# Peripherals.net
KiCad netlist of a schematic drawn in Altium Designer
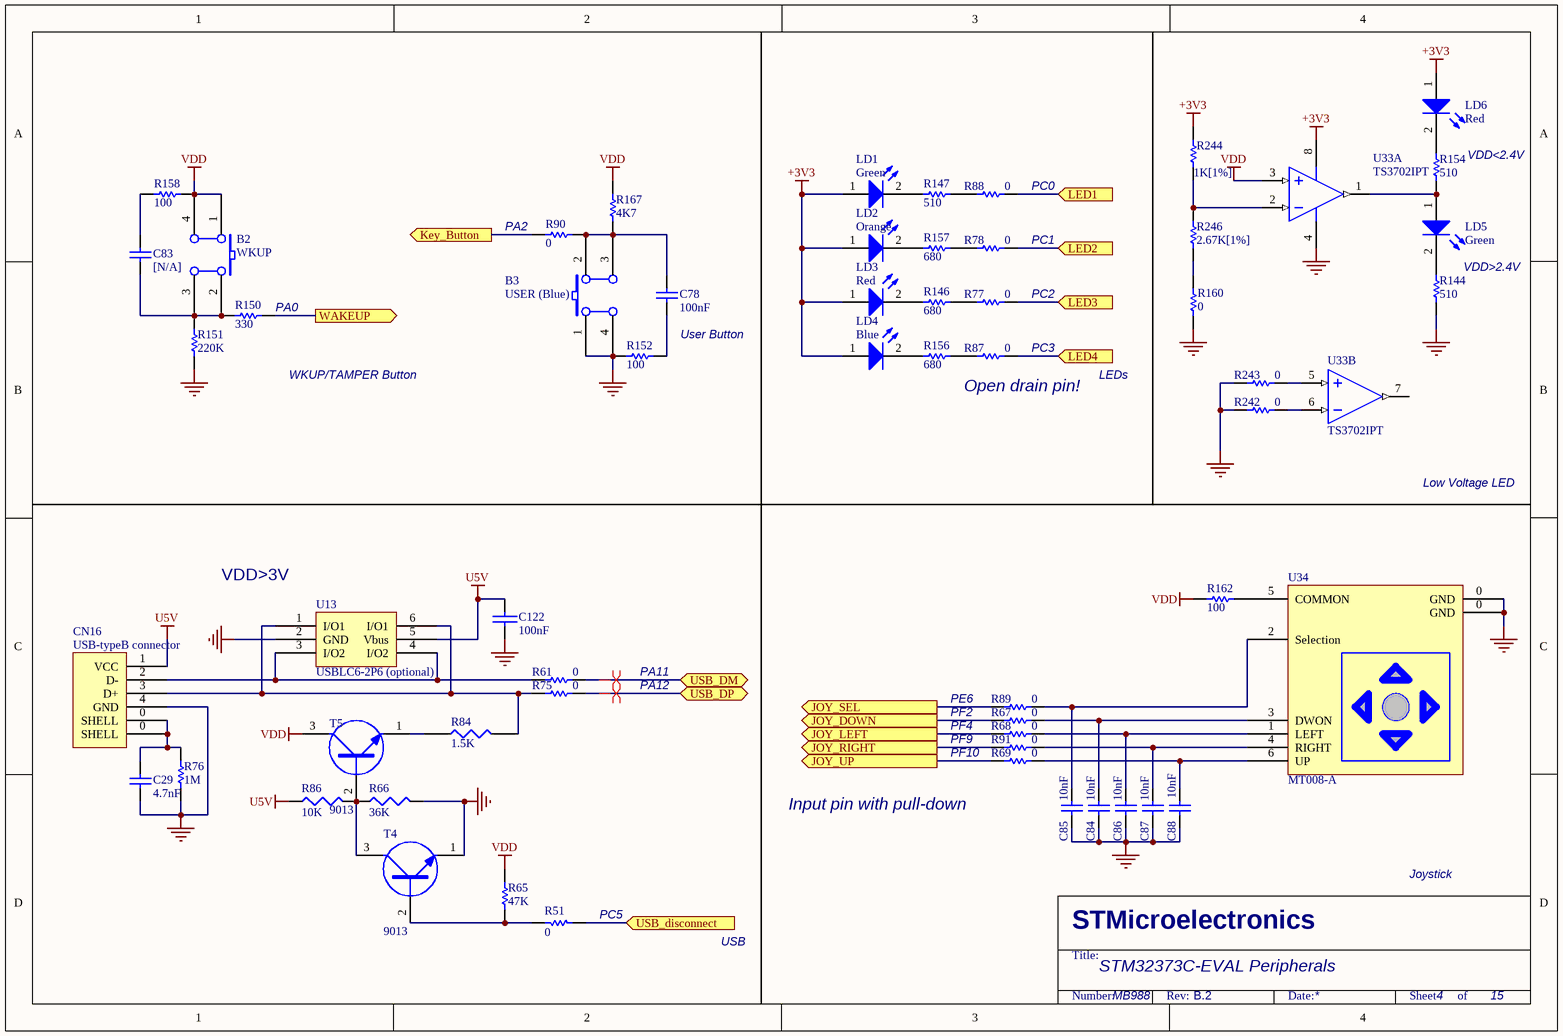
[diagram p0: Peripherals.SchDoc]

(export (version "E")
  (design (tool "Eeschema 10.0.6"))
  (components
    (comp (ref "B2")
      (value "WKUP")
      (footprint "PB10")
      (description "SE PUSHBUTTON")
      (libsource (lib "Documents") (part "SW PUSHBUTTON"))
    )
    (comp (ref "B3")
      (value "USER (Blue)")
      (footprint "PB10")
      (description "SE PUSHBUTTON")
      (libsource (lib "Documents") (part "SW PUSHBUTTON"))
    )
    (comp (ref "C29")
      (value "4.7nF")
      (footprint "0603C")
      (description "Capacitor")
      (fields (field (name "PUBLISHER") "Altium Limited"))
      (libsource (lib "Miscellaneous Devices") (part "CAP"))
    )
    (comp (ref "C78")
      (value "100nF")
      (footprint "0603C")
      (description "Capacitor")
      (fields (field (name "PUBLISHER") "Altium Limited"))
      (libsource (lib "Miscellaneous Devices") (part "CAP"))
    )
    (comp (ref "C83")
      (value "[N/A]")
      (footprint "0603C")
      (description "Capacitor")
      (fields (field (name "PUBLISHER") "Altium Limited"))
      (libsource (lib "Miscellaneous Devices") (part "CAP"))
    )
    (comp (ref "C84")
      (value "10nF")
      (footprint "0603C")
      (description "Capacitor")
      (fields (field (name "PUBLISHER") "Altium Limited"))
      (libsource (lib "Miscellaneous Devices") (part "CAP"))
    )
    (comp (ref "C85")
      (value "10nF")
      (footprint "0603C")
      (description "Capacitor")
      (fields (field (name "PUBLISHER") "Altium Limited"))
      (libsource (lib "Miscellaneous Devices") (part "CAP"))
    )
    (comp (ref "C86")
      (value "10nF")
      (footprint "0603C")
      (description "Capacitor")
      (fields (field (name "PUBLISHER") "Altium Limited"))
      (libsource (lib "Miscellaneous Devices") (part "CAP"))
    )
    (comp (ref "C87")
      (value "10nF")
      (footprint "0603C")
      (description "Capacitor")
      (fields (field (name "PUBLISHER") "Altium Limited"))
      (libsource (lib "Miscellaneous Devices") (part "CAP"))
    )
    (comp (ref "C88")
      (value "10nF")
      (footprint "0603C")
      (description "Capacitor")
      (fields (field (name "PUBLISHER") "Altium Limited"))
      (libsource (lib "Miscellaneous Devices") (part "CAP"))
    )
    (comp (ref "C122")
      (value "100nF")
      (footprint "0603C")
      (description "Capacitor")
      (libsource (lib "*") (part "CAP"))
    )
    (comp (ref "CN16")
      (value "USB-typeB connector")
      (footprint "USB-B")
      (description "USB-B")
      (libsource (lib "Documents") (part "USB-B"))
    )
    (comp (ref "LD1")
      (value "Green")
      (footprint "0603D")
      (description "Typical RED, GREEN, YELLOW, AMBER GaAs LED")
      (fields (field (name "PUBLISHER") "Altium Limited"))
      (libsource (lib "Miscellaneous Devices") (part "LED2"))
    )
    (comp (ref "LD2")
      (value "Orange")
      (footprint "0603D")
      (description "Typical RED, GREEN, YELLOW, AMBER GaAs LED")
      (fields (field (name "PUBLISHER") "Altium Limited"))
      (libsource (lib "Miscellaneous Devices") (part "LED2"))
    )
    (comp (ref "LD3")
      (value "Red")
      (footprint "0603D")
      (description "Typical RED, GREEN, YELLOW, AMBER GaAs LED")
      (fields (field (name "PUBLISHER") "Altium Limited"))
      (libsource (lib "Miscellaneous Devices") (part "LED2"))
    )
    (comp (ref "LD4")
      (value "Blue")
      (footprint "0603D")
      (description "Typical RED, GREEN, YELLOW, AMBER GaAs LED")
      (fields (field (name "PUBLISHER") "Altium Limited"))
      (libsource (lib "Miscellaneous Devices") (part "LED2"))
    )
    (comp (ref "LD5")
      (value "Green")
      (footprint "0603D")
      (description "Typical RED, GREEN, YELLOW, AMBER GaAs LED")
      (fields (field (name "PUBLISHER") "Altium Limited"))
      (libsource (lib "Miscellaneous Devices") (part "LED2"))
    )
    (comp (ref "LD6")
      (value "Red")
      (footprint "0603D")
      (description "Typical RED, GREEN, YELLOW, AMBER GaAs LED")
      (fields (field (name "PUBLISHER") "Altium Limited"))
      (libsource (lib "Miscellaneous Devices") (part "LED2"))
    )
    (comp (ref "R51")
      (value "0")
      (footprint "0603R")
      (description "Resistor")
      (fields (field (name "PUBLISHER") "Altium Limited"))
      (libsource (lib "Miscellaneous Devices") (part "Res1"))
    )
    (comp (ref "R61")
      (value "0")
      (footprint "0603R")
      (description "Resistor")
      (fields (field (name "PUBLISHER") "Altium Limited"))
      (libsource (lib "Miscellaneous Devices") (part "Res1"))
    )
    (comp (ref "R65")
      (value "47K")
      (footprint "0603R")
      (description "Resistor")
      (fields (field (name "PUBLISHER") "Altium Limited"))
      (libsource (lib "Miscellaneous Devices") (part "Res1"))
    )
    (comp (ref "R66") (value "36K") (footprint "0603R") (libsource (lib "*") (part "R")))
    (comp (ref "R67")
      (value "0")
      (footprint "0603R")
      (description "Resistor")
      (fields (field (name "PUBLISHER") "Altium Limited"))
      (libsource (lib "Miscellaneous Devices") (part "Res1"))
    )
    (comp (ref "R68")
      (value "0")
      (footprint "0603R")
      (description "Resistor")
      (fields (field (name "PUBLISHER") "Altium Limited"))
      (libsource (lib "Miscellaneous Devices") (part "Res1"))
    )
    (comp (ref "R69")
      (value "0")
      (footprint "0603R")
      (description "Resistor")
      (fields (field (name "PUBLISHER") "Altium Limited"))
      (libsource (lib "Miscellaneous Devices") (part "Res1"))
    )
    (comp (ref "R75")
      (value "0")
      (footprint "0603R")
      (description "Resistor")
      (fields (field (name "PUBLISHER") "Altium Limited"))
      (libsource (lib "Miscellaneous Devices") (part "Res1"))
    )
    (comp (ref "R76")
      (value "1M")
      (footprint "0603R")
      (description "Resistor")
      (fields (field (name "PUBLISHER") "Altium Limited"))
      (libsource (lib "Miscellaneous Devices") (part "Res1"))
    )
    (comp (ref "R77")
      (value "0")
      (footprint "0603R")
      (description "Resistor")
      (fields (field (name "PUBLISHER") "Altium Limited"))
      (libsource (lib "Miscellaneous Devices") (part "Res1"))
    )
    (comp (ref "R78")
      (value "0")
      (footprint "0603R")
      (description "Resistor")
      (fields (field (name "PUBLISHER") "Altium Limited"))
      (libsource (lib "Miscellaneous Devices") (part "Res1"))
    )
    (comp (ref "R84") (value "1.5K") (footprint "0603R") (libsource (lib "*") (part "RES1")))
    (comp (ref "R86") (value "10K") (footprint "0603R") (libsource (lib "*") (part "R")))
    (comp (ref "R87")
      (value "0")
      (footprint "0603R")
      (description "Resistor")
      (fields (field (name "PUBLISHER") "Altium Limited"))
      (libsource (lib "Miscellaneous Devices") (part "Res1"))
    )
    (comp (ref "R88")
      (value "0")
      (footprint "0603R")
      (description "Resistor")
      (fields (field (name "PUBLISHER") "Altium Limited"))
      (libsource (lib "Miscellaneous Devices") (part "Res1"))
    )
    (comp (ref "R89")
      (value "0")
      (footprint "0603R")
      (description "Resistor")
      (fields (field (name "PUBLISHER") "Altium Limited"))
      (libsource (lib "Miscellaneous Devices") (part "Res1"))
    )
    (comp (ref "R90")
      (value "0")
      (footprint "0603R")
      (description "Resistor")
      (fields (field (name "PUBLISHER") "Altium Limited"))
      (libsource (lib "Miscellaneous Devices") (part "Res1"))
    )
    (comp (ref "R91")
      (value "0")
      (footprint "0603R")
      (description "Resistor")
      (fields (field (name "PUBLISHER") "Altium Limited"))
      (libsource (lib "Miscellaneous Devices") (part "Res1"))
    )
    (comp (ref "R144")
      (value "510")
      (footprint "0603R")
      (description "Resistor")
      (fields (field (name "PUBLISHER") "Altium Limited"))
      (libsource (lib "Miscellaneous Devices") (part "Res1"))
    )
    (comp (ref "R146")
      (value "680")
      (footprint "0603R")
      (description "Resistor")
      (fields (field (name "PUBLISHER") "Altium Limited"))
      (libsource (lib "Miscellaneous Devices") (part "Res1"))
    )
    (comp (ref "R147")
      (value "510")
      (footprint "0603R")
      (description "Resistor")
      (fields (field (name "PUBLISHER") "Altium Limited"))
      (libsource (lib "Miscellaneous Devices") (part "Res1"))
    )
    (comp (ref "R150")
      (value "330")
      (footprint "0603R")
      (description "Resistor")
      (fields (field (name "PUBLISHER") "Altium Limited"))
      (libsource (lib "Miscellaneous Devices") (part "Res1"))
    )
    (comp (ref "R151")
      (value "220K")
      (footprint "0603R")
      (description "Resistor")
      (fields (field (name "PUBLISHER") "Altium Limited"))
      (libsource (lib "Miscellaneous Devices") (part "res1"))
    )
    (comp (ref "R152")
      (value "100")
      (footprint "0603R")
      (description "Resistor")
      (fields (field (name "PUBLISHER") "Altium Limited"))
      (libsource (lib "Miscellaneous Devices") (part "Res1"))
    )
    (comp (ref "R154")
      (value "510")
      (footprint "0603R")
      (description "Resistor")
      (fields (field (name "PUBLISHER") "Altium Limited"))
      (libsource (lib "Miscellaneous Devices") (part "Res1"))
    )
    (comp (ref "R156")
      (value "680")
      (footprint "0603R")
      (description "Resistor")
      (fields (field (name "PUBLISHER") "Altium Limited"))
      (libsource (lib "Miscellaneous Devices") (part "Res1"))
    )
    (comp (ref "R157")
      (value "680")
      (footprint "0603R")
      (description "Resistor")
      (fields (field (name "PUBLISHER") "Altium Limited"))
      (libsource (lib "Miscellaneous Devices") (part "Res1"))
    )
    (comp (ref "R158")
      (value "100")
      (footprint "0603R")
      (description "Resistor")
      (fields (field (name "PUBLISHER") "Altium Limited"))
      (libsource (lib "Miscellaneous Devices") (part "Res1"))
    )
    (comp (ref "R160")
      (value "0")
      (footprint "0603R")
      (description "Resistor")
      (fields (field (name "PUBLISHER") "Altium Limited"))
      (libsource (lib "Miscellaneous Devices") (part "Res1"))
    )
    (comp (ref "R162")
      (value "100")
      (footprint "0603R")
      (description "Resistor")
      (fields (field (name "PUBLISHER") "Altium Limited"))
      (libsource (lib "Miscellaneous Devices") (part "Res1"))
    )
    (comp (ref "R167")
      (value "4K7")
      (footprint "0603R")
      (description "Resistor")
      (fields (field (name "PUBLISHER") "Altium Limited"))
      (libsource (lib "Miscellaneous Devices") (part "res1"))
    )
    (comp (ref "R242")
      (value "0")
      (footprint "0603R")
      (description "Resistor")
      (fields (field (name "PUBLISHER") "Altium Limited"))
      (libsource (lib "Miscellaneous Devices") (part "Res1"))
    )
    (comp (ref "R243")
      (value "0")
      (footprint "0603R")
      (description "Resistor")
      (fields (field (name "PUBLISHER") "Altium Limited"))
      (libsource (lib "Miscellaneous Devices") (part "Res1"))
    )
    (comp (ref "R244")
      (value "1K[1%]")
      (footprint "0603R")
      (description "Resistor")
      (fields (field (name "PUBLISHER") "Altium Limited"))
      (libsource (lib "Miscellaneous Devices") (part "Res1"))
    )
    (comp (ref "R246")
      (value "2.67K[1%]")
      (footprint "0603R")
      (description "Resistor")
      (fields (field (name "PUBLISHER") "Altium Limited"))
      (libsource (lib "Miscellaneous Devices") (part "Res1"))
    )
    (comp (ref "T4") (value "9013") (footprint "SOT-23") (libsource (lib "*") (part "NPN")))
    (comp (ref "T5") (value "9013") (footprint "SOT-23") (libsource (lib "*") (part "NPN")))
    (comp (ref "U13")
      (value "USBLC6-2P6 (optional)")
      (footprint "SOT-666")
      (libsource (lib "STR910_SCHLIB") (part "USBLC6-2"))
    )
    (comp (ref "U33")
      (value "TS3702IPT")
      (footprint "TSSOP8(6.4)")
      (libsource (lib "MB819") (part "LM393PT"))
    )
    (comp (ref "U34") (value "MT008-A") (footprint "JOY") (libsource (lib "MB988") (part "MT-008A")))
  )
  (nets
    (net (code "1") (name "+3V3") (class "Default")
      (node (ref "LD1") (pin "1") (pinfunction "A_1") (pintype "passive"))
      (node (ref "LD2") (pin "1") (pinfunction "A_1") (pintype "passive"))
      (node (ref "LD3") (pin "1") (pinfunction "A_1") (pintype "passive"))
      (node (ref "LD4") (pin "1") (pinfunction "A_1") (pintype "passive"))
      (node (ref "LD6") (pin "1") (pinfunction "A_1") (pintype "passive"))
      (node (ref "R244") (pin "2") (pinfunction "2_2") (pintype "passive"))
      (node (ref "U33") (pin "8") (pinfunction "V+_8") (pintype "power_in"))
    )
    (net (code "2") (name "/JOY_DOWN") (class "Default")
      (node (ref "R67") (pin "2") (pinfunction "2_2") (pintype "passive"))
    )
    (net (code "3") (name "/JOY_LEFT") (class "Default")
      (node (ref "R68") (pin "2") (pinfunction "2_2") (pintype "passive"))
    )
    (net (code "4") (name "/JOY_RIGHT") (class "Default")
      (node (ref "R91") (pin "2") (pinfunction "2_2") (pintype "passive"))
    )
    (net (code "5") (name "/JOY_SEL") (class "Default")
      (node (ref "R89") (pin "2") (pinfunction "2_2") (pintype "passive"))
    )
    (net (code "6") (name "/JOY_UP") (class "Default")
      (node (ref "R69") (pin "2") (pinfunction "2_2") (pintype "passive"))
    )
    (net (code "7") (name "/Key_Button") (class "Default")
      (node (ref "R90") (pin "2") (pinfunction "2_2") (pintype "passive"))
    )
    (net (code "8") (name "/LED1") (class "Default")
      (node (ref "R88") (pin "1") (pinfunction "1_1") (pintype "passive"))
    )
    (net (code "9") (name "/LED2") (class "Default")
      (node (ref "R78") (pin "1") (pinfunction "1_1") (pintype "passive"))
    )
    (net (code "10") (name "/LED3") (class "Default")
      (node (ref "R77") (pin "1") (pinfunction "1_1") (pintype "passive"))
    )
    (net (code "11") (name "/LED4") (class "Default")
      (node (ref "R87") (pin "1") (pinfunction "1_1") (pintype "passive"))
    )
    (net (code "12") (name "/USB_DM") (class "Default")
      (node (ref "R61") (pin "1") (pinfunction "1_1") (pintype "passive"))
    )
    (net (code "13") (name "/USB_DP") (class "Default")
      (node (ref "R75") (pin "1") (pinfunction "1_1") (pintype "passive"))
    )
    (net (code "14") (name "/USB_disconnect") (class "Default")
      (node (ref "R51") (pin "2") (pinfunction "2_2") (pintype "passive"))
    )
    (net (code "15") (name "/WAKEUP") (class "Default")
      (node (ref "R150") (pin "2") (pinfunction "2_2") (pintype "passive"))
    )
    (net (code "16") (name "GND") (class "Default")
      (node (ref "B3") (pin "1") (pinfunction "A0_1") (pintype "passive"))
      (node (ref "B3") (pin "4") (pinfunction "A1_4") (pintype "passive"))
      (node (ref "C122") (pin "2") (pinfunction "2_2") (pintype "passive"))
      (node (ref "C29") (pin "1") (pinfunction "1_1") (pintype "passive"))
      (node (ref "C84") (pin "1") (pinfunction "1_1") (pintype "passive"))
      (node (ref "C85") (pin "1") (pinfunction "1_1") (pintype "passive"))
      (node (ref "C86") (pin "1") (pinfunction "1_1") (pintype "passive"))
      (node (ref "C87") (pin "1") (pinfunction "1_1") (pintype "passive"))
      (node (ref "C88") (pin "1") (pinfunction "1_1") (pintype "passive"))
      (node (ref "CN16") (pin "4") (pinfunction "GND_4") (pintype "passive"))
      (node (ref "R144") (pin "2") (pinfunction "2_2") (pintype "passive"))
      (node (ref "R151") (pin "2") (pinfunction "2_2") (pintype "passive"))
      (node (ref "R152") (pin "1") (pinfunction "1_1") (pintype "passive"))
      (node (ref "R160") (pin "2") (pinfunction "2_2") (pintype "passive"))
      (node (ref "R242") (pin "2") (pinfunction "2_2") (pintype "passive"))
      (node (ref "R243") (pin "2") (pinfunction "2_2") (pintype "passive"))
      (node (ref "R66") (pin "2") (pinfunction "2_2") (pintype "passive"))
      (node (ref "R76") (pin "1") (pinfunction "1_1") (pintype "passive"))
      (node (ref "T4") (pin "1") (pinfunction "E_1") (pintype "passive"))
      (node (ref "U13") (pin "2") (pinfunction "GND_2") (pintype "passive"))
      (node (ref "U33") (pin "4") (pinfunction "V-_4") (pintype "power_in"))
      (node (ref "U34") (pin "0") (pinfunction "GND_0") (pintype "passive"))
    )
    (net (code "17") (name "Net-(B2-B0)") (class "Default")
      (node (ref "B2") (pin "2") (pinfunction "B0_2") (pintype "passive"))
      (node (ref "B2") (pin "3") (pinfunction "B1_3") (pintype "passive"))
      (node (ref "C83") (pin "2") (pinfunction "2_2") (pintype "passive"))
      (node (ref "R150") (pin "1") (pinfunction "1_1") (pintype "passive"))
      (node (ref "R151") (pin "1") (pinfunction "1_1") (pintype "passive"))
    )
    (net (code "18") (name "Net-(B3-B0)") (class "Default")
      (node (ref "B3") (pin "2") (pinfunction "B0_2") (pintype "passive"))
      (node (ref "B3") (pin "3") (pinfunction "B1_3") (pintype "passive"))
      (node (ref "C78") (pin "2") (pinfunction "2_2") (pintype "passive"))
      (node (ref "R167") (pin "1") (pinfunction "1_1") (pintype "passive"))
      (node (ref "R90") (pin "1") (pinfunction "1_1") (pintype "passive"))
    )
    (net (code "19") (name "Net-(C78-Pad1)") (class "Default")
      (node (ref "C78") (pin "1") (pinfunction "1_1") (pintype "passive"))
      (node (ref "R152") (pin "2") (pinfunction "2_2") (pintype "passive"))
    )
    (net (code "20") (name "Net-(C83-Pad1)") (class "Default")
      (node (ref "C83") (pin "1") (pinfunction "1_1") (pintype "passive"))
      (node (ref "R158") (pin "2") (pinfunction "2_2") (pintype "passive"))
    )
    (net (code "21") (name "Net-(CN16-D+)") (class "Default")
      (node (ref "CN16") (pin "3") (pinfunction "D+_3") (pintype "passive"))
      (node (ref "R75") (pin "2") (pinfunction "2_2") (pintype "passive"))
      (node (ref "R84") (pin "2") (pinfunction "2_2") (pintype "passive"))
      (node (ref "U13") (pin "1") (pinfunction "I/O1_1") (pintype "passive"))
      (node (ref "U13") (pin "6") (pinfunction "I/O1_6") (pintype "passive"))
    )
    (net (code "22") (name "Net-(CN16-D-)") (class "Default")
      (node (ref "CN16") (pin "2") (pinfunction "D-_2") (pintype "passive"))
      (node (ref "R61") (pin "2") (pinfunction "2_2") (pintype "passive"))
      (node (ref "U13") (pin "3") (pinfunction "I/O2_3") (pintype "passive"))
      (node (ref "U13") (pin "4") (pinfunction "I/O2_4") (pintype "passive"))
    )
    (net (code "23") (name "Net-(CN16-SHELL)") (class "Default")
      (node (ref "C29") (pin "2") (pinfunction "2_2") (pintype "passive"))
      (node (ref "CN16") (pin "0") (pinfunction "SHELL_0") (pintype "passive"))
      (node (ref "R76") (pin "2") (pinfunction "2_2") (pintype "passive"))
    )
    (net (code "24") (name "Net-(LD1-K)") (class "Default")
      (node (ref "LD1") (pin "2") (pinfunction "K_2") (pintype "passive"))
      (node (ref "R147") (pin "2") (pinfunction "2_2") (pintype "passive"))
    )
    (net (code "25") (name "Net-(LD2-K)") (class "Default")
      (node (ref "LD2") (pin "2") (pinfunction "K_2") (pintype "passive"))
      (node (ref "R157") (pin "2") (pinfunction "2_2") (pintype "passive"))
    )
    (net (code "26") (name "Net-(LD3-K)") (class "Default")
      (node (ref "LD3") (pin "2") (pinfunction "K_2") (pintype "passive"))
      (node (ref "R146") (pin "2") (pinfunction "2_2") (pintype "passive"))
    )
    (net (code "27") (name "Net-(LD4-K)") (class "Default")
      (node (ref "LD4") (pin "2") (pinfunction "K_2") (pintype "passive"))
      (node (ref "R156") (pin "2") (pinfunction "2_2") (pintype "passive"))
    )
    (net (code "28") (name "Net-(LD5-A)") (class "Default")
      (node (ref "LD5") (pin "1") (pinfunction "A_1") (pintype "passive"))
      (node (ref "R154") (pin "2") (pinfunction "2_2") (pintype "passive"))
      (node (ref "U33") (pin "1") (pinfunction "OUT_1") (pintype "output"))
    )
    (net (code "29") (name "Net-(LD5-K)") (class "Default")
      (node (ref "LD5") (pin "2") (pinfunction "K_2") (pintype "passive"))
      (node (ref "R144") (pin "1") (pinfunction "1_1") (pintype "passive"))
    )
    (net (code "30") (name "Net-(LD6-K)") (class "Default")
      (node (ref "LD6") (pin "2") (pinfunction "K_2") (pintype "passive"))
      (node (ref "R154") (pin "1") (pinfunction "1_1") (pintype "passive"))
    )
    (net (code "31") (name "Net-(R146-Pad1)") (class "Default")
      (node (ref "R146") (pin "1") (pinfunction "1_1") (pintype "passive"))
      (node (ref "R77") (pin "2") (pinfunction "2_2") (pintype "passive"))
    )
    (net (code "32") (name "Net-(R147-Pad1)") (class "Default")
      (node (ref "R147") (pin "1") (pinfunction "1_1") (pintype "passive"))
      (node (ref "R88") (pin "2") (pinfunction "2_2") (pintype "passive"))
    )
    (net (code "33") (name "Net-(R156-Pad1)") (class "Default")
      (node (ref "R156") (pin "1") (pinfunction "1_1") (pintype "passive"))
      (node (ref "R87") (pin "2") (pinfunction "2_2") (pintype "passive"))
    )
    (net (code "34") (name "Net-(R157-Pad1)") (class "Default")
      (node (ref "R157") (pin "1") (pinfunction "1_1") (pintype "passive"))
      (node (ref "R78") (pin "2") (pinfunction "2_2") (pintype "passive"))
    )
    (net (code "35") (name "Net-(R160-Pad1)") (class "Default")
      (node (ref "R160") (pin "1") (pinfunction "1_1") (pintype "passive"))
      (node (ref "R246") (pin "1") (pinfunction "1_1") (pintype "passive"))
    )
    (net (code "36") (name "Net-(T4-B)") (class "Default")
      (node (ref "R51") (pin "1") (pinfunction "1_1") (pintype "passive"))
      (node (ref "R65") (pin "1") (pinfunction "1_1") (pintype "passive"))
      (node (ref "T4") (pin "2") (pinfunction "B_2") (pintype "passive"))
    )
    (net (code "37") (name "Net-(T4-C)") (class "Default")
      (node (ref "R66") (pin "1") (pinfunction "1_1") (pintype "passive"))
      (node (ref "R86") (pin "2") (pinfunction "2_2") (pintype "passive"))
      (node (ref "T4") (pin "3") (pinfunction "C_3") (pintype "passive"))
      (node (ref "T5") (pin "2") (pinfunction "B_2") (pintype "passive"))
    )
    (net (code "38") (name "Net-(T5-E)") (class "Default")
      (node (ref "R84") (pin "1") (pinfunction "1_1") (pintype "passive"))
      (node (ref "T5") (pin "1") (pinfunction "E_1") (pintype "passive"))
    )
    (net (code "39") (name "Net-(U33A-IN-)") (class "Default")
      (node (ref "R244") (pin "1") (pinfunction "1_1") (pintype "passive"))
      (node (ref "R246") (pin "2") (pinfunction "2_2") (pintype "passive"))
      (node (ref "U33") (pin "2") (pinfunction "IN-_2") (pintype "input"))
    )
    (net (code "40") (name "Net-(U33B-IN+)") (class "Default")
      (node (ref "R243") (pin "1") (pinfunction "1_1") (pintype "passive"))
      (node (ref "U33") (pin "5") (pinfunction "IN+_5") (pintype "input"))
    )
    (net (code "41") (name "Net-(U33B-IN-)") (class "Default")
      (node (ref "R242") (pin "1") (pinfunction "1_1") (pintype "passive"))
      (node (ref "U33") (pin "6") (pinfunction "IN-_6") (pintype "input"))
    )
    (net (code "42") (name "Net-(U34-COMMON)") (class "Default")
      (node (ref "R162") (pin "2") (pinfunction "2_2") (pintype "passive"))
      (node (ref "U34") (pin "5") (pinfunction "COMMON_5") (pintype "passive"))
    )
    (net (code "43") (name "Net-(U34-DWON)") (class "Default")
      (node (ref "C84") (pin "2") (pinfunction "2_2") (pintype "passive"))
      (node (ref "R67") (pin "1") (pinfunction "1_1") (pintype "passive"))
      (node (ref "U34") (pin "3") (pinfunction "DWON_3") (pintype "passive"))
    )
    (net (code "44") (name "Net-(U34-LEFT)") (class "Default")
      (node (ref "C86") (pin "2") (pinfunction "2_2") (pintype "passive"))
      (node (ref "R68") (pin "1") (pinfunction "1_1") (pintype "passive"))
      (node (ref "U34") (pin "1") (pinfunction "LEFT_1") (pintype "passive"))
    )
    (net (code "45") (name "Net-(U34-RIGHT)") (class "Default")
      (node (ref "C87") (pin "2") (pinfunction "2_2") (pintype "passive"))
      (node (ref "R91") (pin "1") (pinfunction "1_1") (pintype "passive"))
      (node (ref "U34") (pin "4") (pinfunction "RIGHT_4") (pintype "passive"))
    )
    (net (code "46") (name "Net-(U34-Selection)") (class "Default")
      (node (ref "C85") (pin "2") (pinfunction "2_2") (pintype "passive"))
      (node (ref "R89") (pin "1") (pinfunction "1_1") (pintype "passive"))
      (node (ref "U34") (pin "2") (pinfunction "Selection_2") (pintype "passive"))
    )
    (net (code "47") (name "Net-(U34-UP)") (class "Default")
      (node (ref "C88") (pin "2") (pinfunction "2_2") (pintype "passive"))
      (node (ref "R69") (pin "1") (pinfunction "1_1") (pintype "passive"))
      (node (ref "U34") (pin "6") (pinfunction "UP_6") (pintype "passive"))
    )
    (net (code "48") (name "U5V") (class "Default")
      (node (ref "C122") (pin "1") (pinfunction "1_1") (pintype "passive"))
      (node (ref "CN16") (pin "1") (pinfunction "VCC_1") (pintype "passive"))
      (node (ref "R86") (pin "1") (pinfunction "1_1") (pintype "passive"))
      (node (ref "U13") (pin "5") (pinfunction "Vbus_5") (pintype "passive"))
    )
    (net (code "49") (name "VDD") (class "Default")
      (node (ref "B2") (pin "1") (pinfunction "A0_1") (pintype "passive"))
      (node (ref "B2") (pin "4") (pinfunction "A1_4") (pintype "passive"))
      (node (ref "R158") (pin "1") (pinfunction "1_1") (pintype "passive"))
      (node (ref "R162") (pin "1") (pinfunction "1_1") (pintype "passive"))
      (node (ref "R167") (pin "2") (pinfunction "2_2") (pintype "passive"))
      (node (ref "R65") (pin "2") (pinfunction "2_2") (pintype "passive"))
      (node (ref "T5") (pin "3") (pinfunction "C_3") (pintype "passive"))
      (node (ref "U33") (pin "3") (pinfunction "IN+_3") (pintype "input"))
    )
    (net (code "50") (name "unconnected-(U33B-OUT-Pad7)") (class "Default")
      (node (ref "U33") (pin "7") (pinfunction "OUT_7") (pintype "output"))
    )
  )
)
